# core09.net
KiCad netlist of a schematic drawn in EAGLE
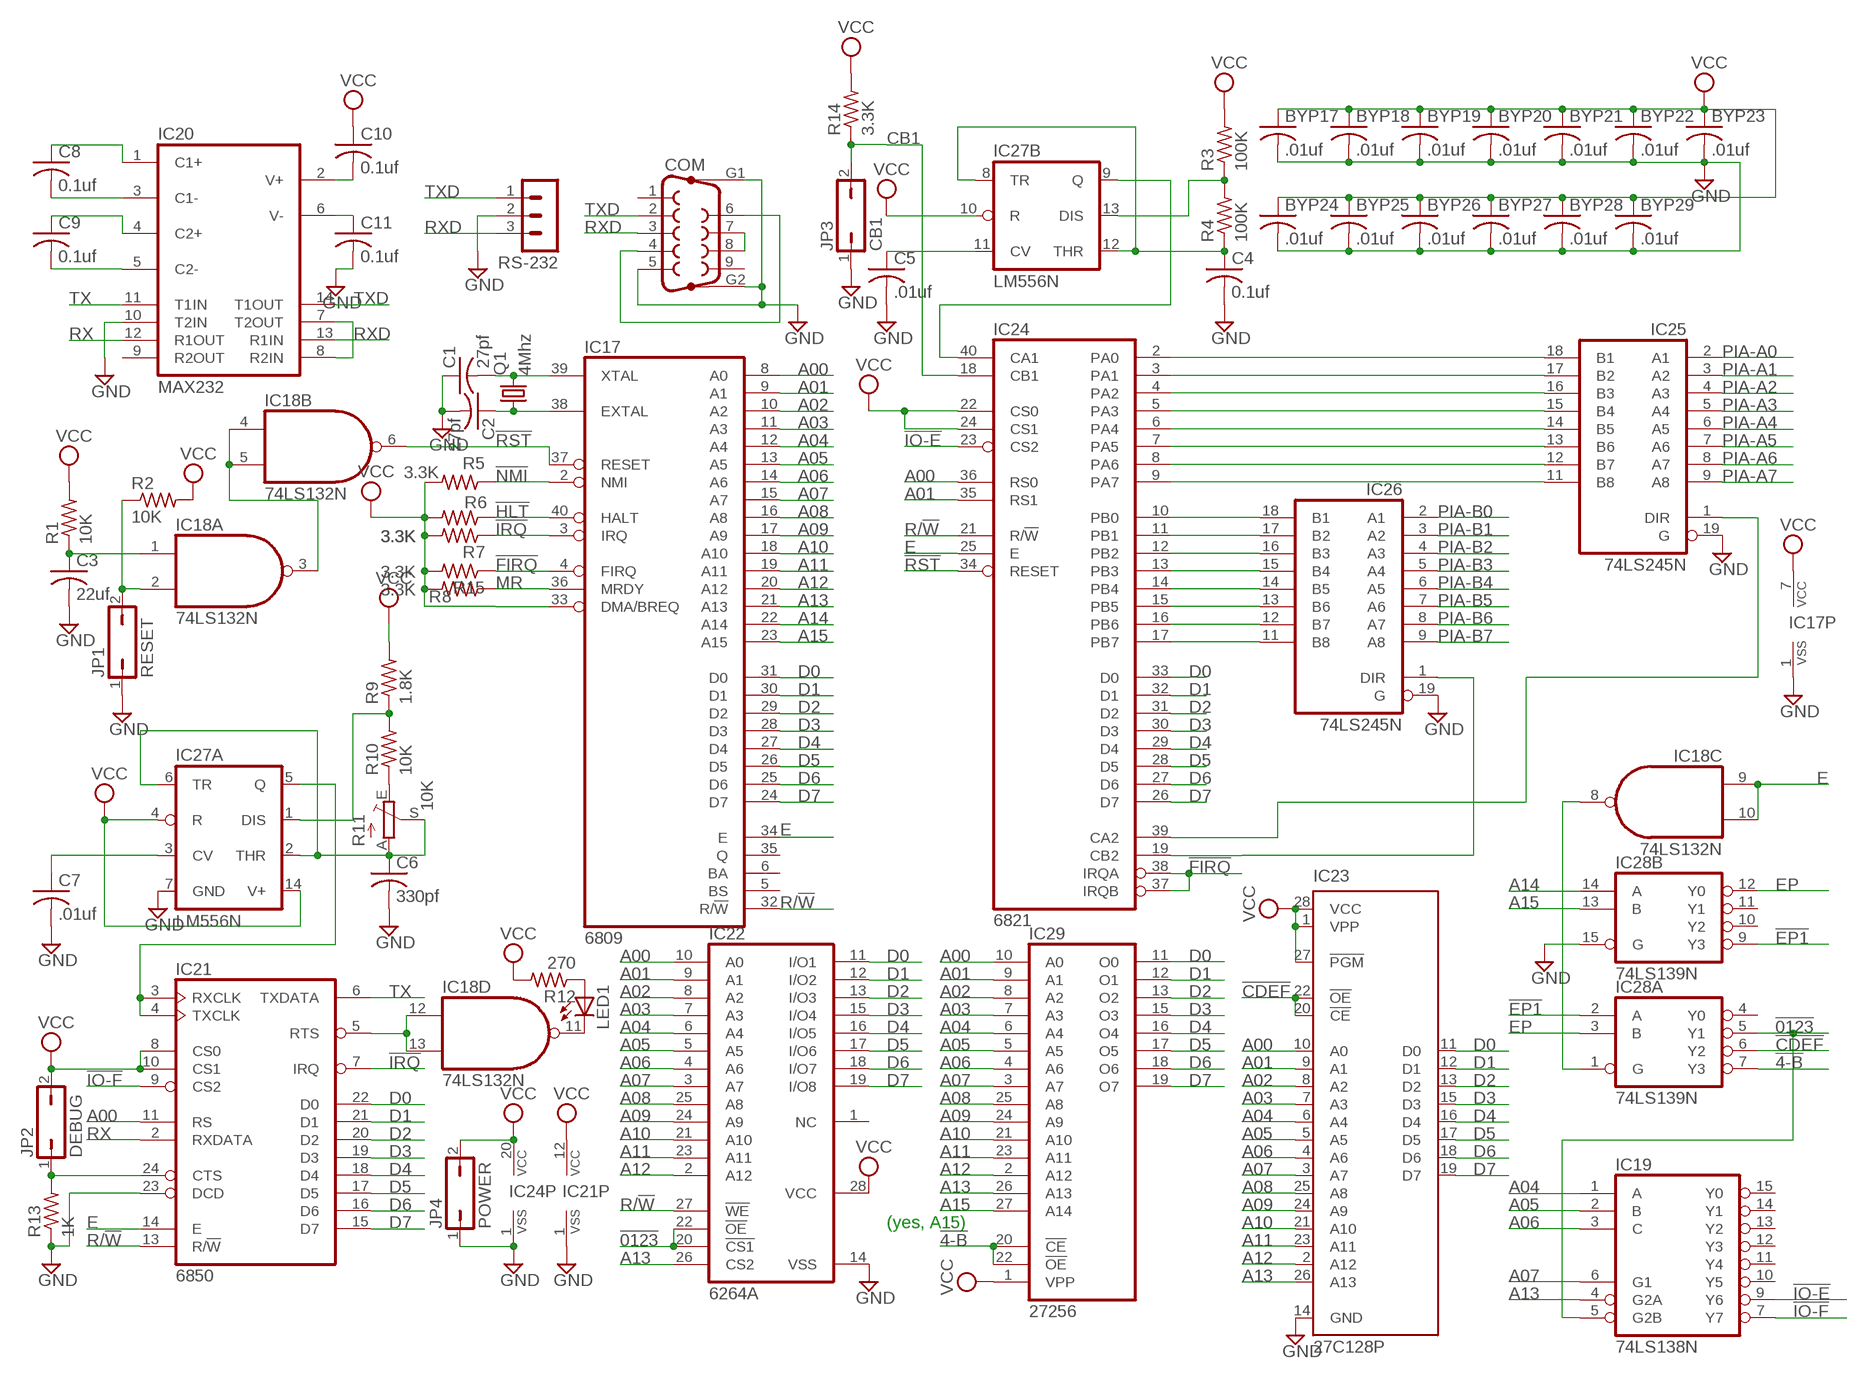
[diagram p0: schematic, sheet 1]
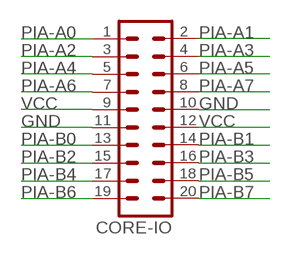
[diagram p1: schematic, sheet 2]

(export (version "E")
  (design (tool "Eeschema 10.0.6"))
  (components
    (comp (ref "BYP17")
      (value ".01uf")
      (footprint "eagle-import:C050-025X075")
      (libsource (lib "eagle-import") (part "C-US050-025X075"))
    )
    (comp (ref "BYP18")
      (value ".01uf")
      (footprint "eagle-import:C050-025X075")
      (libsource (lib "eagle-import") (part "C-US050-025X075"))
    )
    (comp (ref "BYP19")
      (value ".01uf")
      (footprint "eagle-import:C050-025X075")
      (libsource (lib "eagle-import") (part "C-US050-025X075"))
    )
    (comp (ref "BYP20")
      (value ".01uf")
      (footprint "eagle-import:C050-025X075")
      (libsource (lib "eagle-import") (part "C-US050-025X075"))
    )
    (comp (ref "BYP21")
      (value ".01uf")
      (footprint "eagle-import:C050-025X075")
      (libsource (lib "eagle-import") (part "C-US050-025X075"))
    )
    (comp (ref "BYP22")
      (value ".01uf")
      (footprint "eagle-import:C050-025X075")
      (libsource (lib "eagle-import") (part "C-US050-025X075"))
    )
    (comp (ref "BYP23")
      (value ".01uf")
      (footprint "eagle-import:C050-025X075")
      (libsource (lib "eagle-import") (part "C-US050-025X075"))
    )
    (comp (ref "BYP24")
      (value ".01uf")
      (footprint "eagle-import:C050-025X075")
      (libsource (lib "eagle-import") (part "C-US050-025X075"))
    )
    (comp (ref "BYP25")
      (value ".01uf")
      (footprint "eagle-import:C050-025X075")
      (libsource (lib "eagle-import") (part "C-US050-025X075"))
    )
    (comp (ref "BYP26")
      (value ".01uf")
      (footprint "eagle-import:C050-025X075")
      (libsource (lib "eagle-import") (part "C-US050-025X075"))
    )
    (comp (ref "BYP27")
      (value ".01uf")
      (footprint "eagle-import:C050-025X075")
      (libsource (lib "eagle-import") (part "C-US050-025X075"))
    )
    (comp (ref "BYP28")
      (value ".01uf")
      (footprint "eagle-import:C050-025X075")
      (libsource (lib "eagle-import") (part "C-US050-025X075"))
    )
    (comp (ref "BYP29")
      (value ".01uf")
      (footprint "eagle-import:C050-025X075")
      (libsource (lib "eagle-import") (part "C-US050-025X075"))
    )
    (comp (ref "C1")
      (value "27pf")
      (footprint "eagle-import:C050-025X075")
      (libsource (lib "eagle-import") (part "C-US050-025X075"))
    )
    (comp (ref "C2")
      (value "27pf")
      (footprint "eagle-import:C050-025X075")
      (libsource (lib "eagle-import") (part "C-US050-025X075"))
    )
    (comp (ref "C3")
      (value "22uf")
      (footprint "eagle-import:C102-043X133")
      (libsource (lib "eagle-import") (part "C-US102-043X133"))
    )
    (comp (ref "C4")
      (value "0.1uf")
      (footprint "eagle-import:C050-025X075")
      (libsource (lib "eagle-import") (part "C-US050-025X075"))
    )
    (comp (ref "C5")
      (value ".01uf")
      (footprint "eagle-import:C050-025X075")
      (libsource (lib "eagle-import") (part "C-US050-025X075"))
    )
    (comp (ref "C6")
      (value "330pf")
      (footprint "eagle-import:C050-025X075")
      (libsource (lib "eagle-import") (part "C-US050-025X075"))
    )
    (comp (ref "C7")
      (value ".01uf")
      (footprint "eagle-import:C050-025X075")
      (libsource (lib "eagle-import") (part "C-US050-025X075"))
    )
    (comp (ref "C8")
      (value "0.1uf")
      (footprint "eagle-import:C050-025X075")
      (libsource (lib "eagle-import") (part "C-US050-025X075"))
    )
    (comp (ref "C9")
      (value "0.1uf")
      (footprint "eagle-import:C050-025X075")
      (libsource (lib "eagle-import") (part "C-US050-025X075"))
    )
    (comp (ref "C10")
      (value "0.1uf")
      (footprint "eagle-import:C050-025X075")
      (libsource (lib "eagle-import") (part "C-US050-025X075"))
    )
    (comp (ref "C11")
      (value "0.1uf")
      (footprint "eagle-import:C050-025X075")
      (libsource (lib "eagle-import") (part "C-US050-025X075"))
    )
    (comp (ref "COM")
      (value "F09HP")
      (footprint "eagle-import:F09HP")
      (libsource (lib "eagle-import") (part "F09HP"))
    )
    (comp (ref "IC17")
      (value "6809")
      (footprint "eagle-import:DIL40")
      (fields (field (name "MF") "NTE ELECTRONICS") (field (name "MPN") "NTE6809"))
      (libsource (lib "eagle-import") (part "6809"))
    )
    (comp (ref "IC18")
      (value "74LS132N")
      (footprint "eagle-import:DIL14")
      (libsource (lib "eagle-import") (part "7400NLS"))
    )
    (comp (ref "IC19")
      (value "74LS138N")
      (footprint "eagle-import:DIL16")
      (libsource (lib "eagle-import") (part "74138NLS"))
    )
    (comp (ref "IC20")
      (value "MAX232")
      (footprint "eagle-import:DIL16")
      (fields (field (name "MF") "MAXIM") (field (name "MPN") "MAX232ACPE+"))
      (libsource (lib "eagle-import") (part "MAX232"))
    )
    (comp (ref "IC21")
      (value "6850")
      (footprint "eagle-import:DIL24")
      (fields (field (name "MF") "NTE ELECTRONICS") (field (name "MPN") "NTE6850"))
      (libsource (lib "eagle-import") (part "6850"))
    )
    (comp (ref "IC22")
      (value "6264A")
      (footprint "eagle-import:DIL28-6")
      (libsource (lib "eagle-import") (part "6264A"))
    )
    (comp (ref "IC23")
      (value "27C128P")
      (footprint "eagle-import:DIL28-6")
      (libsource (lib "eagle-import") (part "27128PC"))
    )
    (comp (ref "IC24")
      (value "6821")
      (footprint "eagle-import:DIL40")
      (fields (field (name "MF") "NTE ELECTRONICS") (field (name "MPN") "NTE6821"))
      (libsource (lib "eagle-import") (part "6821"))
    )
    (comp (ref "IC25")
      (value "74LS245N")
      (footprint "eagle-import:DIL20")
      (libsource (lib "eagle-import") (part "74245NLS"))
    )
    (comp (ref "IC26")
      (value "74LS245N")
      (footprint "eagle-import:DIL20")
      (libsource (lib "eagle-import") (part "74245NLS"))
    )
    (comp (ref "IC27")
      (value "LM556N")
      (footprint "eagle-import:DIL14")
      (libsource (lib "eagle-import") (part "556NLM"))
    )
    (comp (ref "IC28")
      (value "74LS139N")
      (footprint "eagle-import:DIL16")
      (libsource (lib "eagle-import") (part "74139NLS"))
    )
    (comp (ref "IC29")
      (value "27256")
      (footprint "eagle-import:DIL28")
      (libsource (lib "eagle-import") (part "27256"))
    )
    (comp (ref "JP1")
      (value "RESET")
      (footprint "eagle-import:JP1")
      (libsource (lib "eagle-import") (part "JP1Q"))
    )
    (comp (ref "JP2")
      (value "DEBUG")
      (footprint "eagle-import:JP1")
      (libsource (lib "eagle-import") (part "JP1Q"))
    )
    (comp (ref "JP3")
      (value "CB1")
      (footprint "eagle-import:JP1")
      (libsource (lib "eagle-import") (part "JP1Q"))
    )
    (comp (ref "JP4")
      (value "POWER")
      (footprint "eagle-import:JP1")
      (libsource (lib "eagle-import") (part "JP1Q"))
    )
    (comp (ref "LED1")
      (value "LED3MM")
      (footprint "eagle-import:LED3MM")
      (libsource (lib "eagle-import") (part "LED3MM"))
    )
    (comp (ref "Q1")
      (value "4Mhz")
      (footprint "eagle-import:HC18U-V")
      (libsource (lib "eagle-import") (part "CRYSTALHC18U-V"))
    )
    (comp (ref "R1")
      (value "10K")
      (footprint "eagle-import:0207_7")
      (libsource (lib "eagle-import") (part "R-US_0207/7"))
    )
    (comp (ref "R2")
      (value "10K")
      (footprint "eagle-import:0207_7")
      (libsource (lib "eagle-import") (part "R-US_0207/7"))
    )
    (comp (ref "R3")
      (value "100K")
      (footprint "eagle-import:0207_7")
      (libsource (lib "eagle-import") (part "R-US_0207/7"))
    )
    (comp (ref "R4")
      (value "100K")
      (footprint "eagle-import:0207_7")
      (libsource (lib "eagle-import") (part "R-US_0207/7"))
    )
    (comp (ref "R5")
      (value "3.3K")
      (footprint "eagle-import:0207_7")
      (libsource (lib "eagle-import") (part "R-US_0207/7"))
    )
    (comp (ref "R6")
      (value "3.3K")
      (footprint "eagle-import:0207_7")
      (libsource (lib "eagle-import") (part "R-US_0207/7"))
    )
    (comp (ref "R7")
      (value "3.3K")
      (footprint "eagle-import:0207_7")
      (libsource (lib "eagle-import") (part "R-US_0207/7"))
    )
    (comp (ref "R8")
      (value "3.3K")
      (footprint "eagle-import:0207_7")
      (libsource (lib "eagle-import") (part "R-US_0207/7"))
    )
    (comp (ref "R9")
      (value "1.8K")
      (footprint "eagle-import:0207_7")
      (libsource (lib "eagle-import") (part "R-US_0207/7"))
    )
    (comp (ref "R10")
      (value "10K")
      (footprint "eagle-import:0207_7")
      (libsource (lib "eagle-import") (part "R-US_0207/7"))
    )
    (comp (ref "R11")
      (value "10K")
      (footprint "eagle-import:SP19L")
      (libsource (lib "eagle-import") (part "TRIM_EU-B90P"))
    )
    (comp (ref "R12")
      (value "270")
      (footprint "eagle-import:0207_7")
      (libsource (lib "eagle-import") (part "R-US_0207/7"))
    )
    (comp (ref "R13")
      (value "1K")
      (footprint "eagle-import:0207_7")
      (libsource (lib "eagle-import") (part "R-US_0207/7"))
    )
    (comp (ref "R14")
      (value "3.3K")
      (footprint "eagle-import:0207_7")
      (libsource (lib "eagle-import") (part "R-US_0207/7"))
    )
    (comp (ref "R15")
      (value "3.3K")
      (footprint "eagle-import:0207_7")
      (libsource (lib "eagle-import") (part "R-US_0207/7"))
    )
    (comp (ref "RS-232")
      (value "MA03-1")
      (footprint "eagle-import:MA03-1")
      (libsource (lib "eagle-import") (part "MA03-1"))
    )
    (comp (ref "CORE-IO")
      (value "MA10-2")
      (footprint "eagle-import:MA10-2")
      (libsource (lib "eagle-import") (part "MA10-2"))
    )
  )
  (nets
    (net (code "1") (name "A00") (class "Default")
      (node (ref "IC17") (pin "8") (pinfunction "A0_8") (pintype "tri_state"))
      (node (ref "IC21") (pin "11") (pinfunction "RS_11") (pintype "input"))
      (node (ref "IC22") (pin "10") (pinfunction "A0_10") (pintype "input"))
      (node (ref "IC23") (pin "10") (pinfunction "A0_10") (pintype "input"))
      (node (ref "IC24") (pin "36") (pinfunction "RS0_36") (pintype "input"))
      (node (ref "IC29") (pin "10") (pinfunction "A0_10") (pintype "input"))
    )
    (net (code "2") (name "A01") (class "Default")
      (node (ref "IC17") (pin "9") (pinfunction "A1_9") (pintype "tri_state"))
      (node (ref "IC22") (pin "9") (pinfunction "A1_9") (pintype "input"))
      (node (ref "IC23") (pin "9") (pinfunction "A1_9") (pintype "input"))
      (node (ref "IC24") (pin "35") (pinfunction "RS1_35") (pintype "input"))
      (node (ref "IC29") (pin "9") (pinfunction "A1_9") (pintype "input"))
    )
    (net (code "3") (name "A02") (class "Default")
      (node (ref "IC17") (pin "10") (pinfunction "A2_10") (pintype "tri_state"))
      (node (ref "IC22") (pin "8") (pinfunction "A2_8") (pintype "input"))
      (node (ref "IC23") (pin "8") (pinfunction "A2_8") (pintype "input"))
      (node (ref "IC29") (pin "8") (pinfunction "A2_8") (pintype "input"))
    )
    (net (code "4") (name "A03") (class "Default")
      (node (ref "IC17") (pin "11") (pinfunction "A3_11") (pintype "tri_state"))
      (node (ref "IC22") (pin "7") (pinfunction "A3_7") (pintype "input"))
      (node (ref "IC23") (pin "7") (pinfunction "A3_7") (pintype "input"))
      (node (ref "IC29") (pin "7") (pinfunction "A3_7") (pintype "input"))
    )
    (net (code "5") (name "A04") (class "Default")
      (node (ref "IC17") (pin "12") (pinfunction "A4_12") (pintype "tri_state"))
      (node (ref "IC19") (pin "1") (pinfunction "A_1") (pintype "input"))
      (node (ref "IC22") (pin "6") (pinfunction "A4_6") (pintype "input"))
      (node (ref "IC23") (pin "6") (pinfunction "A4_6") (pintype "input"))
      (node (ref "IC29") (pin "6") (pinfunction "A4_6") (pintype "input"))
    )
    (net (code "6") (name "A05") (class "Default")
      (node (ref "IC17") (pin "13") (pinfunction "A5_13") (pintype "tri_state"))
      (node (ref "IC19") (pin "2") (pinfunction "B_2") (pintype "input"))
      (node (ref "IC22") (pin "5") (pinfunction "A5_5") (pintype "input"))
      (node (ref "IC23") (pin "5") (pinfunction "A5_5") (pintype "input"))
      (node (ref "IC29") (pin "5") (pinfunction "A5_5") (pintype "input"))
    )
    (net (code "7") (name "A06") (class "Default")
      (node (ref "IC17") (pin "14") (pinfunction "A6_14") (pintype "tri_state"))
      (node (ref "IC19") (pin "3") (pinfunction "C_3") (pintype "input"))
      (node (ref "IC22") (pin "4") (pinfunction "A6_4") (pintype "input"))
      (node (ref "IC23") (pin "4") (pinfunction "A6_4") (pintype "input"))
      (node (ref "IC29") (pin "4") (pinfunction "A6_4") (pintype "input"))
    )
    (net (code "8") (name "A07") (class "Default")
      (node (ref "IC17") (pin "15") (pinfunction "A7_15") (pintype "tri_state"))
      (node (ref "IC19") (pin "6") (pinfunction "G1_6") (pintype "input"))
      (node (ref "IC22") (pin "3") (pinfunction "A7_3") (pintype "input"))
      (node (ref "IC23") (pin "3") (pinfunction "A7_3") (pintype "input"))
      (node (ref "IC29") (pin "3") (pinfunction "A7_3") (pintype "input"))
    )
    (net (code "9") (name "A08") (class "Default")
      (node (ref "IC17") (pin "16") (pinfunction "A8_16") (pintype "tri_state"))
      (node (ref "IC22") (pin "25") (pinfunction "A8_25") (pintype "input"))
      (node (ref "IC23") (pin "25") (pinfunction "A8_25") (pintype "input"))
      (node (ref "IC29") (pin "25") (pinfunction "A8_25") (pintype "input"))
    )
    (net (code "10") (name "A09") (class "Default")
      (node (ref "IC17") (pin "17") (pinfunction "A9_17") (pintype "tri_state"))
      (node (ref "IC22") (pin "24") (pinfunction "A9_24") (pintype "input"))
      (node (ref "IC23") (pin "24") (pinfunction "A9_24") (pintype "input"))
      (node (ref "IC29") (pin "24") (pinfunction "A9_24") (pintype "input"))
    )
    (net (code "11") (name "A10") (class "Default")
      (node (ref "IC17") (pin "18") (pinfunction "A10_18") (pintype "tri_state"))
      (node (ref "IC22") (pin "21") (pinfunction "A10_21") (pintype "input"))
      (node (ref "IC23") (pin "21") (pinfunction "A10_21") (pintype "input"))
      (node (ref "IC29") (pin "21") (pinfunction "A10_21") (pintype "input"))
    )
    (net (code "12") (name "A11") (class "Default")
      (node (ref "IC17") (pin "19") (pinfunction "A11_19") (pintype "tri_state"))
      (node (ref "IC22") (pin "23") (pinfunction "A11_23") (pintype "input"))
      (node (ref "IC23") (pin "23") (pinfunction "A11_23") (pintype "input"))
      (node (ref "IC29") (pin "23") (pinfunction "A11_23") (pintype "input"))
    )
    (net (code "13") (name "A12") (class "Default")
      (node (ref "IC17") (pin "20") (pinfunction "A12_20") (pintype "tri_state"))
      (node (ref "IC22") (pin "2") (pinfunction "A12_2") (pintype "input"))
      (node (ref "IC23") (pin "2") (pinfunction "A12_2") (pintype "input"))
      (node (ref "IC29") (pin "2") (pinfunction "A12_2") (pintype "input"))
    )
    (net (code "14") (name "A13") (class "Default")
      (node (ref "IC17") (pin "21") (pinfunction "A13_21") (pintype "tri_state"))
      (node (ref "IC19") (pin "4") (pinfunction "G2A_4") (pintype "input"))
      (node (ref "IC22") (pin "26") (pinfunction "CS2_26") (pintype "input"))
      (node (ref "IC23") (pin "26") (pinfunction "A13_26") (pintype "input"))
      (node (ref "IC29") (pin "26") (pinfunction "A13_26") (pintype "input"))
    )
    (net (code "15") (name "A14") (class "Default")
      (node (ref "IC17") (pin "22") (pinfunction "A14_22") (pintype "tri_state"))
      (node (ref "IC28") (pin "14") (pinfunction "A_14") (pintype "input"))
    )
    (net (code "16") (name "A15") (class "Default")
      (node (ref "IC17") (pin "23") (pinfunction "A15_23") (pintype "tri_state"))
      (node (ref "IC28") (pin "13") (pinfunction "B_13") (pintype "input"))
      (node (ref "IC29") (pin "27") (pinfunction "A14_27") (pintype "input"))
    )
    (net (code "17") (name "CB1") (class "Default")
      (node (ref "IC24") (pin "18") (pinfunction "CB1_18") (pintype "input"))
      (node (ref "JP3") (pin "2") (pinfunction "2_2") (pintype "passive"))
      (node (ref "R14") (pin "1") (pinfunction "1_1") (pintype "passive"))
    )
    (net (code "18") (name "D0") (class "Default")
      (node (ref "IC17") (pin "31") (pinfunction "D0_31") (pintype "bidirectional"))
      (node (ref "IC21") (pin "22") (pinfunction "D0_22") (pintype "bidirectional"))
      (node (ref "IC22") (pin "11") (pinfunction "I/O1_11") (pintype "bidirectional"))
      (node (ref "IC23") (pin "11") (pinfunction "D0_11") (pintype "tri_state"))
      (node (ref "IC24") (pin "33") (pinfunction "D0_33") (pintype "bidirectional"))
      (node (ref "IC29") (pin "11") (pinfunction "O0_11") (pintype "tri_state"))
    )
    (net (code "19") (name "D1") (class "Default")
      (node (ref "IC17") (pin "30") (pinfunction "D1_30") (pintype "bidirectional"))
      (node (ref "IC21") (pin "21") (pinfunction "D1_21") (pintype "bidirectional"))
      (node (ref "IC22") (pin "12") (pinfunction "I/O2_12") (pintype "bidirectional"))
      (node (ref "IC23") (pin "12") (pinfunction "D1_12") (pintype "tri_state"))
      (node (ref "IC24") (pin "32") (pinfunction "D1_32") (pintype "bidirectional"))
      (node (ref "IC29") (pin "12") (pinfunction "O1_12") (pintype "tri_state"))
    )
    (net (code "20") (name "D2") (class "Default")
      (node (ref "IC17") (pin "29") (pinfunction "D2_29") (pintype "bidirectional"))
      (node (ref "IC21") (pin "20") (pinfunction "D2_20") (pintype "bidirectional"))
      (node (ref "IC22") (pin "13") (pinfunction "I/O3_13") (pintype "bidirectional"))
      (node (ref "IC23") (pin "13") (pinfunction "D2_13") (pintype "tri_state"))
      (node (ref "IC24") (pin "31") (pinfunction "D2_31") (pintype "bidirectional"))
      (node (ref "IC29") (pin "13") (pinfunction "O2_13") (pintype "tri_state"))
    )
    (net (code "21") (name "D3") (class "Default")
      (node (ref "IC17") (pin "28") (pinfunction "D3_28") (pintype "bidirectional"))
      (node (ref "IC21") (pin "19") (pinfunction "D3_19") (pintype "bidirectional"))
      (node (ref "IC22") (pin "15") (pinfunction "I/O4_15") (pintype "bidirectional"))
      (node (ref "IC23") (pin "15") (pinfunction "D3_15") (pintype "tri_state"))
      (node (ref "IC24") (pin "30") (pinfunction "D3_30") (pintype "bidirectional"))
      (node (ref "IC29") (pin "15") (pinfunction "O3_15") (pintype "tri_state"))
    )
    (net (code "22") (name "D4") (class "Default")
      (node (ref "IC17") (pin "27") (pinfunction "D4_27") (pintype "bidirectional"))
      (node (ref "IC21") (pin "18") (pinfunction "D4_18") (pintype "bidirectional"))
      (node (ref "IC22") (pin "16") (pinfunction "I/O5_16") (pintype "bidirectional"))
      (node (ref "IC23") (pin "16") (pinfunction "D4_16") (pintype "tri_state"))
      (node (ref "IC24") (pin "29") (pinfunction "D4_29") (pintype "bidirectional"))
      (node (ref "IC29") (pin "16") (pinfunction "O4_16") (pintype "tri_state"))
    )
    (net (code "23") (name "D5") (class "Default")
      (node (ref "IC17") (pin "26") (pinfunction "D5_26") (pintype "bidirectional"))
      (node (ref "IC21") (pin "17") (pinfunction "D5_17") (pintype "bidirectional"))
      (node (ref "IC22") (pin "17") (pinfunction "I/O6_17") (pintype "bidirectional"))
      (node (ref "IC23") (pin "17") (pinfunction "D5_17") (pintype "tri_state"))
      (node (ref "IC24") (pin "28") (pinfunction "D5_28") (pintype "bidirectional"))
      (node (ref "IC29") (pin "17") (pinfunction "O5_17") (pintype "tri_state"))
    )
    (net (code "24") (name "D6") (class "Default")
      (node (ref "IC17") (pin "25") (pinfunction "D6_25") (pintype "bidirectional"))
      (node (ref "IC21") (pin "16") (pinfunction "D6_16") (pintype "bidirectional"))
      (node (ref "IC22") (pin "18") (pinfunction "I/O7_18") (pintype "bidirectional"))
      (node (ref "IC23") (pin "18") (pinfunction "D6_18") (pintype "tri_state"))
      (node (ref "IC24") (pin "27") (pinfunction "D6_27") (pintype "bidirectional"))
      (node (ref "IC29") (pin "18") (pinfunction "O6_18") (pintype "tri_state"))
    )
    (net (code "25") (name "D7") (class "Default")
      (node (ref "IC17") (pin "24") (pinfunction "D7_24") (pintype "bidirectional"))
      (node (ref "IC21") (pin "15") (pinfunction "D7_15") (pintype "bidirectional"))
      (node (ref "IC22") (pin "19") (pinfunction "I/O8_19") (pintype "bidirectional"))
      (node (ref "IC23") (pin "19") (pinfunction "D7_19") (pintype "tri_state"))
      (node (ref "IC24") (pin "26") (pinfunction "D7_26") (pintype "bidirectional"))
      (node (ref "IC29") (pin "19") (pinfunction "O7_19") (pintype "tri_state"))
    )
    (net (code "26") (name "E") (class "Default")
      (node (ref "IC17") (pin "34") (pinfunction "E_34") (pintype "output"))
      (node (ref "IC18") (pin "10") (pinfunction "I1_10") (pintype "input"))
      (node (ref "IC18") (pin "9") (pinfunction "I0_9") (pintype "input"))
      (node (ref "IC21") (pin "14") (pinfunction "E_14") (pintype "input"))
      (node (ref "IC24") (pin "25") (pinfunction "E_25") (pintype "input"))
    )
    (net (code "27") (name "EP") (class "Default")
      (node (ref "IC28") (pin "12") (pinfunction "Y0_12") (pintype "output"))
      (node (ref "IC28") (pin "3") (pinfunction "B_3") (pintype "input"))
    )
    (net (code "28") (name "GND") (class "Default")
      (node (ref "BYP17") (pin "2") (pinfunction "2_2") (pintype "passive"))
      (node (ref "BYP18") (pin "2") (pinfunction "2_2") (pintype "passive"))
      (node (ref "BYP19") (pin "2") (pinfunction "2_2") (pintype "passive"))
      (node (ref "BYP20") (pin "2") (pinfunction "2_2") (pintype "passive"))
      (node (ref "BYP21") (pin "2") (pinfunction "2_2") (pintype "passive"))
      (node (ref "BYP22") (pin "2") (pinfunction "2_2") (pintype "passive"))
      (node (ref "BYP23") (pin "2") (pinfunction "2_2") (pintype "passive"))
      (node (ref "BYP24") (pin "2") (pinfunction "2_2") (pintype "passive"))
      (node (ref "BYP25") (pin "2") (pinfunction "2_2") (pintype "passive"))
      (node (ref "BYP26") (pin "2") (pinfunction "2_2") (pintype "passive"))
      (node (ref "BYP27") (pin "2") (pinfunction "2_2") (pintype "passive"))
      (node (ref "BYP28") (pin "2") (pinfunction "2_2") (pintype "passive"))
      (node (ref "BYP29") (pin "2") (pinfunction "2_2") (pintype "passive"))
      (node (ref "C1") (pin "1") (pinfunction "1_1") (pintype "passive"))
      (node (ref "C11") (pin "2") (pinfunction "2_2") (pintype "passive"))
      (node (ref "C2") (pin "2") (pinfunction "2_2") (pintype "passive"))
      (node (ref "C3") (pin "2") (pinfunction "2_2") (pintype "passive"))
      (node (ref "C4") (pin "2") (pinfunction "2_2") (pintype "passive"))
      (node (ref "C5") (pin "2") (pinfunction "2_2") (pintype "passive"))
      (node (ref "C6") (pin "2") (pinfunction "2_2") (pintype "passive"))
      (node (ref "C7") (pin "2") (pinfunction "2_2") (pintype "passive"))
      (node (ref "COM") (pin "5") (pinfunction "5_5") (pintype "passive"))
      (node (ref "COM") (pin "G1") (pinfunction "G1_G1") (pintype "passive"))
      (node (ref "COM") (pin "G2") (pinfunction "G2_G2") (pintype "passive"))
      (node (ref "CORE-IO") (pin "10") (pinfunction "10_10") (pintype "passive"))
      (node (ref "CORE-IO") (pin "11") (pinfunction "11_11") (pintype "passive"))
      (node (ref "IC17") (pin "1") (pinfunction "VSS_1") (pintype "power_in"))
      (node (ref "IC20") (pin "10") (pinfunction "T2IN_10") (pintype "input"))
      (node (ref "IC21") (pin "1") (pinfunction "VSS_1") (pintype "power_in"))
      (node (ref "IC21") (pin "23") (pinfunction "DCD_23") (pintype "input"))
      (node (ref "IC22") (pin "14") (pinfunction "VSS_14") (pintype "power_in"))
      (node (ref "IC23") (pin "14") (pinfunction "GND_14") (pintype "power_in"))
      (node (ref "IC24") (pin "1") (pinfunction "VSS_1") (pintype "power_in"))
      (node (ref "IC25") (pin "19") (pinfunction "G_19") (pintype "input"))
      (node (ref "IC26") (pin "19") (pinfunction "G_19") (pintype "input"))
      (node (ref "IC27") (pin "7") (pinfunction "GND_7") (pintype "power_in"))
      (node (ref "IC28") (pin "15") (pinfunction "G_15") (pintype "input"))
      (node (ref "JP1") (pin "1") (pinfunction "1_1") (pintype "passive"))
      (node (ref "JP3") (pin "1") (pinfunction "1_1") (pintype "passive"))
      (node (ref "JP4") (pin "1") (pinfunction "1_1") (pintype "passive"))
      (node (ref "R13") (pin "1") (pinfunction "1_1") (pintype "passive"))
      (node (ref "RS-232") (pin "2") (pinfunction "2_2") (pintype "passive"))
    )
    (net (code "29") (name "MR") (class "Default")
      (node (ref "IC17") (pin "36") (pinfunction "MRDY_36") (pintype "input"))
      (node (ref "R8") (pin "1") (pinfunction "1_1") (pintype "passive"))
    )
    (net (code "30") (name "Net-(COM-Pad4)") (class "Default")
      (node (ref "COM") (pin "4") (pinfunction "4_4") (pintype "passive"))
      (node (ref "COM") (pin "6") (pinfunction "6_6") (pintype "passive"))
    )
    (net (code "31") (name "Net-(COM-Pad7)") (class "Default")
      (node (ref "COM") (pin "7") (pinfunction "7_7") (pintype "passive"))
      (node (ref "COM") (pin "8") (pinfunction "8_8") (pintype "passive"))
    )
    (net (code "32") (name "Net-(IC17A-EXTAL)") (class "Default")
      (node (ref "C2") (pin "1") (pinfunction "1_1") (pintype "passive"))
      (node (ref "IC17") (pin "38") (pinfunction "EXTAL_38") (pintype "input"))
      (node (ref "Q1") (pin "1") (pinfunction "1_1") (pintype "passive"))
    )
    (net (code "33") (name "Net-(IC17A-XTAL)") (class "Default")
      (node (ref "C1") (pin "2") (pinfunction "2_2") (pintype "passive"))
      (node (ref "IC17") (pin "39") (pinfunction "XTAL_39") (pintype "input"))
      (node (ref "Q1") (pin "2") (pinfunction "2_2") (pintype "passive"))
    )
    (net (code "34") (name "Net-(IC18A-I0)") (class "Default")
      (node (ref "C3") (pin "1") (pinfunction "1_1") (pintype "passive"))
      (node (ref "IC18") (pin "1") (pinfunction "I0_1") (pintype "input"))
      (node (ref "R1") (pin "1") (pinfunction "1_1") (pintype "passive"))
    )
    (net (code "35") (name "Net-(IC18A-I1)") (class "Default")
      (node (ref "IC18") (pin "2") (pinfunction "I1_2") (pintype "input"))
      (node (ref "JP1") (pin "2") (pinfunction "2_2") (pintype "passive"))
      (node (ref "R2") (pin "1") (pinfunction "1_1") (pintype "passive"))
    )
    (net (code "36") (name "Net-(IC18A-O)") (class "Default")
      (node (ref "IC18") (pin "3") (pinfunction "O_3") (pintype "output"))
      (node (ref "IC18") (pin "4") (pinfunction "I0_4") (pintype "input"))
      (node (ref "IC18") (pin "5") (pinfunction "I1_5") (pintype "input"))
    )
    (net (code "37") (name "Net-(IC18C-O)") (class "Default")
      (node (ref "IC18") (pin "8") (pinfunction "O_8") (pintype "output"))
      (node (ref "IC28") (pin "1") (pinfunction "G_1") (pintype "input"))
    )
    (net (code "38") (name "Net-(IC18D-I0)") (class "Default")
      (node (ref "IC18") (pin "12") (pinfunction "I0_12") (pintype "input"))
      (node (ref "IC18") (pin "13") (pinfunction "I1_13") (pintype "input"))
      (node (ref "IC21") (pin "5") (pinfunction "RTS_5") (pintype "output"))
    )
    (net (code "39") (name "Net-(IC18D-O)") (class "Default")
      (node (ref "IC18") (pin "11") (pinfunction "O_11") (pintype "output"))
      (node (ref "LED1") (pin "K") (pinfunction "C_K") (pintype "passive"))
    )
    (net (code "40") (name "Net-(IC20A-C1+)") (class "Default")
      (node (ref "C8") (pin "1") (pinfunction "1_1") (pintype "passive"))
      (node (ref "IC20") (pin "1") (pinfunction "C1+_1") (pintype "bidirectional"))
    )
    (net (code "41") (name "Net-(IC20A-C1-)") (class "Default")
      (node (ref "C8") (pin "2") (pinfunction "2_2") (pintype "passive"))
      (node (ref "IC20") (pin "3") (pinfunction "C1-_3") (pintype "bidirectional"))
    )
    (net (code "42") (name "Net-(IC20A-C2+)") (class "Default")
      (node (ref "C9") (pin "1") (pinfunction "1_1") (pintype "passive"))
      (node (ref "IC20") (pin "4") (pinfunction "C2+_4") (pintype "bidirectional"))
    )
    (net (code "43") (name "Net-(IC20A-C2-)") (class "Default")
      (node (ref "C9") (pin "2") (pinfunction "2_2") (pintype "passive"))
      (node (ref "IC20") (pin "5") (pinfunction "C2-_5") (pintype "bidirectional"))
    )
    (net (code "44") (name "Net-(IC20A-R2IN)") (class "Default")
      (node (ref "IC20") (pin "7") (pinfunction "T2OUT_7") (pintype "output"))
      (node (ref "IC20") (pin "8") (pinfunction "R2IN_8") (pintype "input"))
    )
    (net (code "45") (name "Net-(IC20A-V+)") (class "Default")
      (node (ref "C10") (pin "2") (pinfunction "2_2") (pintype "passive"))
      (node (ref "IC20") (pin "2") (pinfunction "V+_2") (pintype "bidirectional"))
    )
    (net (code "46") (name "Net-(IC20A-V-)") (class "Default")
      (node (ref "C11") (pin "1") (pinfunction "1_1") (pintype "passive"))
      (node (ref "IC20") (pin "6") (pinfunction "V-_6") (pintype "bidirectional"))
    )
    (net (code "47") (name "Net-(IC21A-CTS)") (class "Default")
      (node (ref "IC21") (pin "24") (pinfunction "CTS_24") (pintype "input"))
      (node (ref "JP2") (pin "1") (pinfunction "1_1") (pintype "passive"))
      (node (ref "R13") (pin "2") (pinfunction "2_2") (pintype "passive"))
    )
    (net (code "48") (name "Net-(IC21A-RXCLK)") (class "Default")
      (node (ref "IC21") (pin "3") (pinfunction "RXCLK_3") (pintype "input"))
      (node (ref "IC21") (pin "4") (pinfunction "TXCLK_4") (pintype "input"))
      (node (ref "IC27") (pin "5") (pinfunction "Q_5") (pintype "output"))
    )
    (net (code "49") (name "Net-(IC24A-CA1)") (class "Default")
      (node (ref "IC24") (pin "40") (pinfunction "CA1_40") (pintype "input"))
      (node (ref "IC27") (pin "9") (pinfunction "Q_9") (pintype "output"))
    )
    (net (code "50") (name "Net-(IC24A-CA2)") (class "Default")
      (node (ref "IC24") (pin "39") (pinfunction "CA2_39") (pintype "bidirectional"))
      (node (ref "IC25") (pin "1") (pinfunction "DIR_1") (pintype "input"))
    )
    (net (code "51") (name "Net-(IC24A-CB2)") (class "Default")
      (node (ref "IC24") (pin "19") (pinfunction "CB2_19") (pintype "bidirectional"))
      (node (ref "IC26") (pin "1") (pinfunction "DIR_1") (pintype "input"))
    )
    (net (code "52") (name "Net-(IC24A-PA0)") (class "Default")
      (node (ref "IC24") (pin "2") (pinfunction "PA0_2") (pintype "bidirectional"))
      (node (ref "IC25") (pin "18") (pinfunction "B1_18") (pintype "bidirectional"))
    )
    (net (code "53") (name "Net-(IC24A-PA1)") (class "Default")
      (node (ref "IC24") (pin "3") (pinfunction "PA1_3") (pintype "bidirectional"))
      (node (ref "IC25") (pin "17") (pinfunction "B2_17") (pintype "bidirectional"))
    )
    (net (code "54") (name "Net-(IC24A-PA2)") (class "Default")
      (node (ref "IC24") (pin "4") (pinfunction "PA2_4") (pintype "bidirectional"))
      (node (ref "IC25") (pin "16") (pinfunction "B3_16") (pintype "bidirectional"))
    )
    (net (code "55") (name "Net-(IC24A-PA3)") (class "Default")
      (node (ref "IC24") (pin "5") (pinfunction "PA3_5") (pintype "bidirectional"))
      (node (ref "IC25") (pin "15") (pinfunction "B4_15") (pintype "bidirectional"))
    )
    (net (code "56") (name "Net-(IC24A-PA4)") (class "Default")
      (node (ref "IC24") (pin "6") (pinfunction "PA4_6") (pintype "bidirectional"))
      (node (ref "IC25") (pin "14") (pinfunction "B5_14") (pintype "bidirectional"))
    )
    (net (code "57") (name "Net-(IC24A-PA5)") (class "Default")
      (node (ref "IC24") (pin "7") (pinfunction "PA5_7") (pintype "bidirectional"))
      (node (ref "IC25") (pin "13") (pinfunction "B6_13") (pintype "bidirectional"))
    )
    (net (code "58") (name "Net-(IC24A-PA6)") (class "Default")
      (node (ref "IC24") (pin "8") (pinfunction "PA6_8") (pintype "bidirectional"))
      (node (ref "IC25") (pin "12") (pinfunction "B7_12") (pintype "bidirectional"))
    )
    (net (code "59") (name "Net-(IC24A-PA7)") (class "Default")
      (node (ref "IC24") (pin "9") (pinfunction "PA7_9") (pintype "bidirectional"))
      (node (ref "IC25") (pin "11") (pinfunction "B8_11") (pintype "bidirectional"))
    )
    (net (code "60") (name "Net-(IC24A-PB0)") (class "Default")
      (node (ref "IC24") (pin "10") (pinfunction "PB0_10") (pintype "bidirectional"))
      (node (ref "IC26") (pin "18") (pinfunction "B1_18") (pintype "bidirectional"))
    )
    (net (code "61") (name "Net-(IC24A-PB1)") (class "Default")
      (node (ref "IC24") (pin "11") (pinfunction "PB1_11") (pintype "bidirectional"))
      (node (ref "IC26") (pin "17") (pinfunction "B2_17") (pintype "bidirectional"))
    )
    (net (code "62") (name "Net-(IC24A-PB2)") (class "Default")
      (node (ref "IC24") (pin "12") (pinfunction "PB2_12") (pintype "bidirectional"))
      (node (ref "IC26") (pin "16") (pinfunction "B3_16") (pintype "bidirectional"))
    )
    (net (code "63") (name "Net-(IC24A-PB3)") (class "Default")
      (node (ref "IC24") (pin "13") (pinfunction "PB3_13") (pintype "bidirectional"))
      (node (ref "IC26") (pin "15") (pinfunction "B4_15") (pintype "bidirectional"))
    )
    (net (code "64") (name "Net-(IC24A-PB4)") (class "Default")
      (node (ref "IC24") (pin "14") (pinfunction "PB4_14") (pintype "bidirectional"))
      (node (ref "IC26") (pin "14") (pinfunction "B5_14") (pintype "bidirectional"))
    )
    (net (code "65") (name "Net-(IC24A-PB5)") (class "Default")
      (node (ref "IC24") (pin "15") (pinfunction "PB5_15") (pintype "bidirectional"))
      (node (ref "IC26") (pin "13") (pinfunction "B6_13") (pintype "bidirectional"))
    )
    (net (code "66") (name "Net-(IC24A-PB6)") (class "Default")
      (node (ref "IC24") (pin "16") (pinfunction "PB6_16") (pintype "bidirectional"))
      (node (ref "IC26") (pin "12") (pinfunction "B7_12") (pintype "bidirectional"))
    )
    (net (code "67") (name "Net-(IC24A-PB7)") (class "Default")
      (node (ref "IC24") (pin "17") (pinfunction "PB7_17") (pintype "bidirectional"))
      (node (ref "IC26") (pin "11") (pinfunction "B8_11") (pintype "bidirectional"))
    )
    (net (code "68") (name "Net-(IC27A-CV)") (class "Default")
      (node (ref "C7") (pin "1") (pinfunction "1_1") (pintype "passive"))
      (node (ref "IC27") (pin "3") (pinfunction "CV_3") (pintype "input"))
    )
    (net (code "69") (name "Net-(IC27A-DIS)") (class "Default")
      (node (ref "IC27") (pin "1") (pinfunction "DIS_1") (pintype "input"))
      (node (ref "R10") (pin "2") (pinfunction "2_2") (pintype "passive"))
      (node (ref "R9") (pin "1") (pinfunction "1_1") (pintype "passive"))
    )
    (net (code "70") (name "Net-(IC27A-THR)") (class "Default")
      (node (ref "C6") (pin "1") (pinfunction "1_1") (pintype "passive"))
      (node (ref "IC27") (pin "2") (pinfunction "THR_2") (pintype "input"))
      (node (ref "IC27") (pin "6") (pinfunction "TR_6") (pintype "input"))
      (node (ref "R11") (pin "A") (pinfunction "A_A") (pintype "passive"))
      (node (ref "R11") (pin "S") (pinfunction "S_S") (pintype "passive"))
    )
    (net (code "71") (name "Net-(IC27B-CV)") (class "Default")
      (node (ref "C5") (pin "1") (pinfunction "1_1") (pintype "passive"))
      (node (ref "IC27") (pin "11") (pinfunction "CV_11") (pintype "input"))
    )
    (net (code "72") (name "Net-(IC27B-DIS)") (class "Default")
      (node (ref "IC27") (pin "13") (pinfunction "DIS_13") (pintype "input"))
      (node (ref "R3") (pin "1") (pinfunction "1_1") (pintype "passive"))
      (node (ref "R4") (pin "2") (pinfunction "2_2") (pintype "passive"))
    )
    (net (code "73") (name "Net-(IC27B-THR)") (class "Default")
      (node (ref "C4") (pin "1") (pinfunction "1_1") (pintype "passive"))
      (node (ref "IC27") (pin "12") (pinfunction "THR_12") (pintype "input"))
      (node (ref "IC27") (pin "8") (pinfunction "TR_8") (pintype "input"))
      (node (ref "R4") (pin "1") (pinfunction "1_1") (pintype "passive"))
    )
    (net (code "74") (name "Net-(LED1-PadA)") (class "Default")
      (node (ref "LED1") (pin "A") (pinfunction "A_A") (pintype "passive"))
      (node (ref "R12") (pin "1") (pinfunction "1_1") (pintype "passive"))
    )
    (net (code "75") (name "Net-(R10-Pad1)") (class "Default")
      (node (ref "R10") (pin "1") (pinfunction "1_1") (pintype "passive"))
      (node (ref "R11") (pin "E") (pinfunction "E_E") (pintype "passive"))
    )
    (net (code "76") (name "PIA-A0") (class "Default")
      (node (ref "CORE-IO") (pin "1") (pinfunction "1_1") (pintype "passive"))
      (node (ref "IC25") (pin "2") (pinfunction "A1_2") (pintype "bidirectional"))
    )
    (net (code "77") (name "PIA-A1") (class "Default")
      (node (ref "CORE-IO") (pin "2") (pinfunction "2_2") (pintype "passive"))
      (node (ref "IC25") (pin "3") (pinfunction "A2_3") (pintype "bidirectional"))
    )
    (net (code "78") (name "PIA-A2") (class "Default")
      (node (ref "CORE-IO") (pin "3") (pinfunction "3_3") (pintype "passive"))
      (node (ref "IC25") (pin "4") (pinfunction "A3_4") (pintype "bidirectional"))
    )
    (net (code "79") (name "PIA-A3") (class "Default")
      (node (ref "CORE-IO") (pin "4") (pinfunction "4_4") (pintype "passive"))
      (node (ref "IC25") (pin "5") (pinfunction "A4_5") (pintype "bidirectional"))
    )
    (net (code "80") (name "PIA-A4") (class "Default")
      (node (ref "CORE-IO") (pin "5") (pinfunction "5_5") (pintype "passive"))
      (node (ref "IC25") (pin "6") (pinfunction "A5_6") (pintype "bidirectional"))
    )
    (net (code "81") (name "PIA-A5") (class "Default")
      (node (ref "CORE-IO") (pin "6") (pinfunction "6_6") (pintype "passive"))
      (node (ref "IC25") (pin "7") (pinfunction "A6_7") (pintype "bidirectional"))
    )
    (net (code "82") (name "PIA-A6") (class "Default")
      (node (ref "CORE-IO") (pin "7") (pinfunction "7_7") (pintype "passive"))
      (node (ref "IC25") (pin "8") (pinfunction "A7_8") (pintype "bidirectional"))
    )
    (net (code "83") (name "PIA-A7") (class "Default")
      (node (ref "CORE-IO") (pin "8") (pinfunction "8_8") (pintype "passive"))
      (node (ref "IC25") (pin "9") (pinfunction "A8_9") (pintype "bidirectional"))
    )
    (net (code "84") (name "PIA-B0") (class "Default")
      (node (ref "CORE-IO") (pin "13") (pinfunction "13_13") (pintype "passive"))
      (node (ref "IC26") (pin "2") (pinfunction "A1_2") (pintype "bidirectional"))
    )
    (net (code "85") (name "PIA-B1") (class "Default")
      (node (ref "CORE-IO") (pin "14") (pinfunction "14_14") (pintype "passive"))
      (node (ref "IC26") (pin "3") (pinfunction "A2_3") (pintype "bidirectional"))
    )
    (net (code "86") (name "PIA-B2") (class "Default")
      (node (ref "CORE-IO") (pin "15") (pinfunction "15_15") (pintype "passive"))
      (node (ref "IC26") (pin "4") (pinfunction "A3_4") (pintype "bidirectional"))
    )
    (net (code "87") (name "PIA-B3") (class "Default")
      (node (ref "CORE-IO") (pin "16") (pinfunction "16_16") (pintype "passive"))
      (node (ref "IC26") (pin "5") (pinfunction "A4_5") (pintype "bidirectional"))
    )
    (net (code "88") (name "PIA-B4") (class "Default")
      (node (ref "CORE-IO") (pin "17") (pinfunction "17_17") (pintype "passive"))
      (node (ref "IC26") (pin "6") (pinfunction "A5_6") (pintype "bidirectional"))
    )
    (net (code "89") (name "PIA-B5") (class "Default")
      (node (ref "CORE-IO") (pin "18") (pinfunction "18_18") (pintype "passive"))
      (node (ref "IC26") (pin "7") (pinfunction "A6_7") (pintype "bidirectional"))
    )
    (net (code "90") (name "PIA-B6") (class "Default")
      (node (ref "CORE-IO") (pin "19") (pinfunction "19_19") (pintype "passive"))
      (node (ref "IC26") (pin "8") (pinfunction "A7_8") (pintype "bidirectional"))
    )
    (net (code "91") (name "PIA-B7") (class "Default")
      (node (ref "CORE-IO") (pin "20") (pinfunction "20_20") (pintype "passive"))
      (node (ref "IC26") (pin "9") (pinfunction "A8_9") (pintype "bidirectional"))
    )
    (net (code "92") (name "RX") (class "Default")
      (node (ref "IC20") (pin "12") (pinfunction "R1OUT_12") (pintype "output"))
      (node (ref "IC21") (pin "2") (pinfunction "RXDATA_2") (pintype "input"))
    )
    (net (code "93") (name "RXD") (class "Default")
      (node (ref "COM") (pin "3") (pinfunction "3_3") (pintype "passive"))
      (node (ref "IC20") (pin "13") (pinfunction "R1IN_13") (pintype "input"))
      (node (ref "RS-232") (pin "3") (pinfunction "3_3") (pintype "passive"))
    )
    (net (code "94") (name "R{slash}~{W}") (class "Default")
      (node (ref "IC17") (pin "32") (pinfunction "R/~{W}_32") (pintype "output"))
      (node (ref "IC21") (pin "13") (pinfunction "R/~{W}_13") (pintype "input"))
      (node (ref "IC22") (pin "27") (pinfunction "~{WE}_27") (pintype "input"))
      (node (ref "IC24") (pin "21") (pinfunction "R/~{W}_21") (pintype "input"))
    )
    (net (code "95") (name "TX") (class "Default")
      (node (ref "IC20") (pin "11") (pinfunction "T1IN_11") (pintype "input"))
      (node (ref "IC21") (pin "6") (pinfunction "TXDATA_6") (pintype "output"))
    )
    (net (code "96") (name "TXD") (class "Default")
      (node (ref "COM") (pin "2") (pinfunction "2_2") (pintype "passive"))
      (node (ref "IC20") (pin "14") (pinfunction "T1OUT_14") (pintype "output"))
      (node (ref "RS-232") (pin "1") (pinfunction "1_1") (pintype "passive"))
    )
    (net (code "97") (name "VCC") (class "Default")
      (node (ref "BYP17") (pin "1") (pinfunction "1_1") (pintype "passive"))
      (node (ref "BYP18") (pin "1") (pinfunction "1_1") (pintype "passive"))
      (node (ref "BYP19") (pin "1") (pinfunction "1_1") (pintype "passive"))
      (node (ref "BYP20") (pin "1") (pinfunction "1_1") (pintype "passive"))
      (node (ref "BYP21") (pin "1") (pinfunction "1_1") (pintype "passive"))
      (node (ref "BYP22") (pin "1") (pinfunction "1_1") (pintype "passive"))
      (node (ref "BYP23") (pin "1") (pinfunction "1_1") (pintype "passive"))
      (node (ref "BYP24") (pin "1") (pinfunction "1_1") (pintype "passive"))
      (node (ref "BYP25") (pin "1") (pinfunction "1_1") (pintype "passive"))
      (node (ref "BYP26") (pin "1") (pinfunction "1_1") (pintype "passive"))
      (node (ref "BYP27") (pin "1") (pinfunction "1_1") (pintype "passive"))
      (node (ref "BYP28") (pin "1") (pinfunction "1_1") (pintype "passive"))
      (node (ref "BYP29") (pin "1") (pinfunction "1_1") (pintype "passive"))
      (node (ref "C10") (pin "1") (pinfunction "1_1") (pintype "passive"))
      (node (ref "CORE-IO") (pin "12") (pinfunction "12_12") (pintype "passive"))
      (node (ref "CORE-IO") (pin "9") (pinfunction "9_9") (pintype "passive"))
      (node (ref "IC17") (pin "33") (pinfunction "DMA/BREQ_33") (pintype "input"))
      (node (ref "IC17") (pin "7") (pinfunction "VCC_7") (pintype "power_in"))
      (node (ref "IC21") (pin "10") (pinfunction "CS1_10") (pintype "input"))
      (node (ref "IC21") (pin "12") (pinfunction "VCC_12") (pintype "power_in"))
      (node (ref "IC21") (pin "8") (pinfunction "CS0_8") (pintype "input"))
      (node (ref "IC22") (pin "28") (pinfunction "VCC_28") (pintype "power_in"))
      (node (ref "IC23") (pin "1") (pinfunction "VPP_1") (pintype "input"))
      (node (ref "IC23") (pin "27") (pinfunction "~{PGM}_27") (pintype "passive"))
      (node (ref "IC23") (pin "28") (pinfunction "VCC_28") (pintype "power_in"))
      (node (ref "IC24") (pin "20") (pinfunction "VCC_20") (pintype "power_in"))
      (node (ref "IC24") (pin "22") (pinfunction "CS0_22") (pintype "input"))
      (node (ref "IC24") (pin "24") (pinfunction "CS1_24") (pintype "input"))
      (node (ref "IC27") (pin "10") (pinfunction "R_10") (pintype "input"))
      (node (ref "IC27") (pin "14") (pinfunction "V+_14") (pintype "power_in"))
      (node (ref "IC27") (pin "4") (pinfunction "R_4") (pintype "input"))
      (node (ref "IC29") (pin "1") (pinfunction "VPP_1") (pintype "input"))
      (node (ref "JP2") (pin "2") (pinfunction "2_2") (pintype "passive"))
      (node (ref "JP4") (pin "2") (pinfunction "2_2") (pintype "passive"))
      (node (ref "R1") (pin "2") (pinfunction "2_2") (pintype "passive"))
      (node (ref "R12") (pin "2") (pinfunction "2_2") (pintype "passive"))
      (node (ref "R14") (pin "2") (pinfunction "2_2") (pintype "passive"))
      (node (ref "R15") (pin "2") (pinfunction "2_2") (pintype "passive"))
      (node (ref "R2") (pin "2") (pinfunction "2_2") (pintype "passive"))
      (node (ref "R3") (pin "2") (pinfunction "2_2") (pintype "passive"))
      (node (ref "R5") (pin "2") (pinfunction "2_2") (pintype "passive"))
      (node (ref "R6") (pin "2") (pinfunction "2_2") (pintype "passive"))
      (node (ref "R7") (pin "2") (pinfunction "2_2") (pintype "passive"))
      (node (ref "R8") (pin "2") (pinfunction "2_2") (pintype "passive"))
      (node (ref "R9") (pin "2") (pinfunction "2_2") (pintype "passive"))
    )
    (net (code "98") (name "unconnected-(COM-Pad1)") (class "Default")
      (node (ref "COM") (pin "1") (pinfunction "1_1") (pintype "passive"))
    )
    (net (code "99") (name "unconnected-(COM-Pad9)") (class "Default")
      (node (ref "COM") (pin "9") (pinfunction "9_9") (pintype "passive"))
    )
    (net (code "100") (name "unconnected-(IC17A-BA-Pad6)") (class "Default")
      (node (ref "IC17") (pin "6") (pinfunction "BA_6") (pintype "output"))
    )
    (net (code "101") (name "unconnected-(IC17A-BS-Pad5)") (class "Default")
      (node (ref "IC17") (pin "5") (pinfunction "BS_5") (pintype "output"))
    )
    (net (code "102") (name "unconnected-(IC17A-Q-Pad35)") (class "Default")
      (node (ref "IC17") (pin "35") (pinfunction "Q_35") (pintype "output"))
    )
    (net (code "103") (name "unconnected-(IC19A-Y0-Pad15)") (class "Default")
      (node (ref "IC19") (pin "15") (pinfunction "Y0_15") (pintype "output"))
    )
    (net (code "104") (name "unconnected-(IC19A-Y1-Pad14)") (class "Default")
      (node (ref "IC19") (pin "14") (pinfunction "Y1_14") (pintype "output"))
    )
    (net (code "105") (name "unconnected-(IC19A-Y2-Pad13)") (class "Default")
      (node (ref "IC19") (pin "13") (pinfunction "Y2_13") (pintype "output"))
    )
    (net (code "106") (name "unconnected-(IC19A-Y3-Pad12)") (class "Default")
      (node (ref "IC19") (pin "12") (pinfunction "Y3_12") (pintype "output"))
    )
    (net (code "107") (name "unconnected-(IC19A-Y4-Pad11)") (class "Default")
      (node (ref "IC19") (pin "11") (pinfunction "Y4_11") (pintype "output"))
    )
    (net (code "108") (name "unconnected-(IC19A-Y5-Pad10)") (class "Default")
      (node (ref "IC19") (pin "10") (pinfunction "Y5_10") (pintype "output"))
    )
    (net (code "109") (name "unconnected-(IC20A-R2OUT-Pad9)") (class "Default")
      (node (ref "IC20") (pin "9") (pinfunction "R2OUT_9") (pintype "output"))
    )
    (net (code "110") (name "unconnected-(IC22-NC-Pad1)") (class "Default")
      (node (ref "IC22") (pin "1") (pinfunction "NC_1") (pintype "no_connect"))
    )
    (net (code "111") (name "unconnected-(IC28A-Y0-Pad4)") (class "Default")
      (node (ref "IC28") (pin "4") (pinfunction "Y0_4") (pintype "output"))
    )
    (net (code "112") (name "unconnected-(IC28B-Y1-Pad11)") (class "Default")
      (node (ref "IC28") (pin "11") (pinfunction "Y1_11") (pintype "output"))
    )
    (net (code "113") (name "unconnected-(IC28B-Y2-Pad10)") (class "Default")
      (node (ref "IC28") (pin "10") (pinfunction "Y2_10") (pintype "output"))
    )
    (net (code "114") (name "~{4-B}") (class "Default")
      (node (ref "IC28") (pin "7") (pinfunction "Y3_7") (pintype "output"))
      (node (ref "IC29") (pin "20") (pinfunction "~{CE}_20") (pintype "input"))
      (node (ref "IC29") (pin "22") (pinfunction "~{OE}_22") (pintype "input"))
    )
    (net (code "115") (name "~{0123}") (class "Default")
      (node (ref "IC19") (pin "5") (pinfunction "G2B_5") (pintype "input"))
      (node (ref "IC22") (pin "20") (pinfunction "~{CS1}_20") (pintype "input"))
      (node (ref "IC22") (pin "22") (pinfunction "~{OE}_22") (pintype "input"))
      (node (ref "IC28") (pin "5") (pinfunction "Y1_5") (pintype "output"))
    )
    (net (code "116") (name "~{CDEF}") (class "Default")
      (node (ref "IC23") (pin "20") (pinfunction "~{CE}_20") (pintype "input"))
      (node (ref "IC23") (pin "22") (pinfunction "~{OE}_22") (pintype "input"))
      (node (ref "IC28") (pin "6") (pinfunction "Y2_6") (pintype "output"))
    )
    (net (code "117") (name "~{EP1}") (class "Default")
      (node (ref "IC28") (pin "2") (pinfunction "A_2") (pintype "input"))
      (node (ref "IC28") (pin "9") (pinfunction "Y3_9") (pintype "output"))
    )
    (net (code "118") (name "~{FIRQ}") (class "Default")
      (node (ref "IC17") (pin "4") (pinfunction "FIRQ_4") (pintype "input"))
      (node (ref "IC24") (pin "37") (pinfunction "IRQB_37") (pintype "open_collector"))
      (node (ref "IC24") (pin "38") (pinfunction "IRQA_38") (pintype "open_collector"))
      (node (ref "R15") (pin "1") (pinfunction "1_1") (pintype "passive"))
    )
    (net (code "119") (name "~{HLT}") (class "Default")
      (node (ref "IC17") (pin "40") (pinfunction "HALT_40") (pintype "input"))
      (node (ref "R5") (pin "1") (pinfunction "1_1") (pintype "passive"))
    )
    (net (code "120") (name "~{IO-E}") (class "Default")
      (node (ref "IC19") (pin "9") (pinfunction "Y6_9") (pintype "output"))
      (node (ref "IC24") (pin "23") (pinfunction "CS2_23") (pintype "input"))
    )
    (net (code "121") (name "~{IO-F}") (class "Default")
      (node (ref "IC19") (pin "7") (pinfunction "Y7_7") (pintype "output"))
      (node (ref "IC21") (pin "9") (pinfunction "CS2_9") (pintype "input"))
    )
    (net (code "122") (name "~{IRQ}") (class "Default")
      (node (ref "IC17") (pin "3") (pinfunction "IRQ_3") (pintype "input"))
      (node (ref "IC21") (pin "7") (pinfunction "IRQ_7") (pintype "output"))
      (node (ref "R7") (pin "1") (pinfunction "1_1") (pintype "passive"))
    )
    (net (code "123") (name "~{NMI}") (class "Default")
      (node (ref "IC17") (pin "2") (pinfunction "NMI_2") (pintype "input"))
      (node (ref "R6") (pin "1") (pinfunction "1_1") (pintype "passive"))
    )
    (net (code "124") (name "~{RST}") (class "Default")
      (node (ref "IC17") (pin "37") (pinfunction "RESET_37") (pintype "input"))
      (node (ref "IC18") (pin "6") (pinfunction "O_6") (pintype "output"))
      (node (ref "IC24") (pin "34") (pinfunction "RESET_34") (pintype "input"))
    )
  )
)
